# servos.net
KiCad netlist of a schematic drawn in Altium Designer
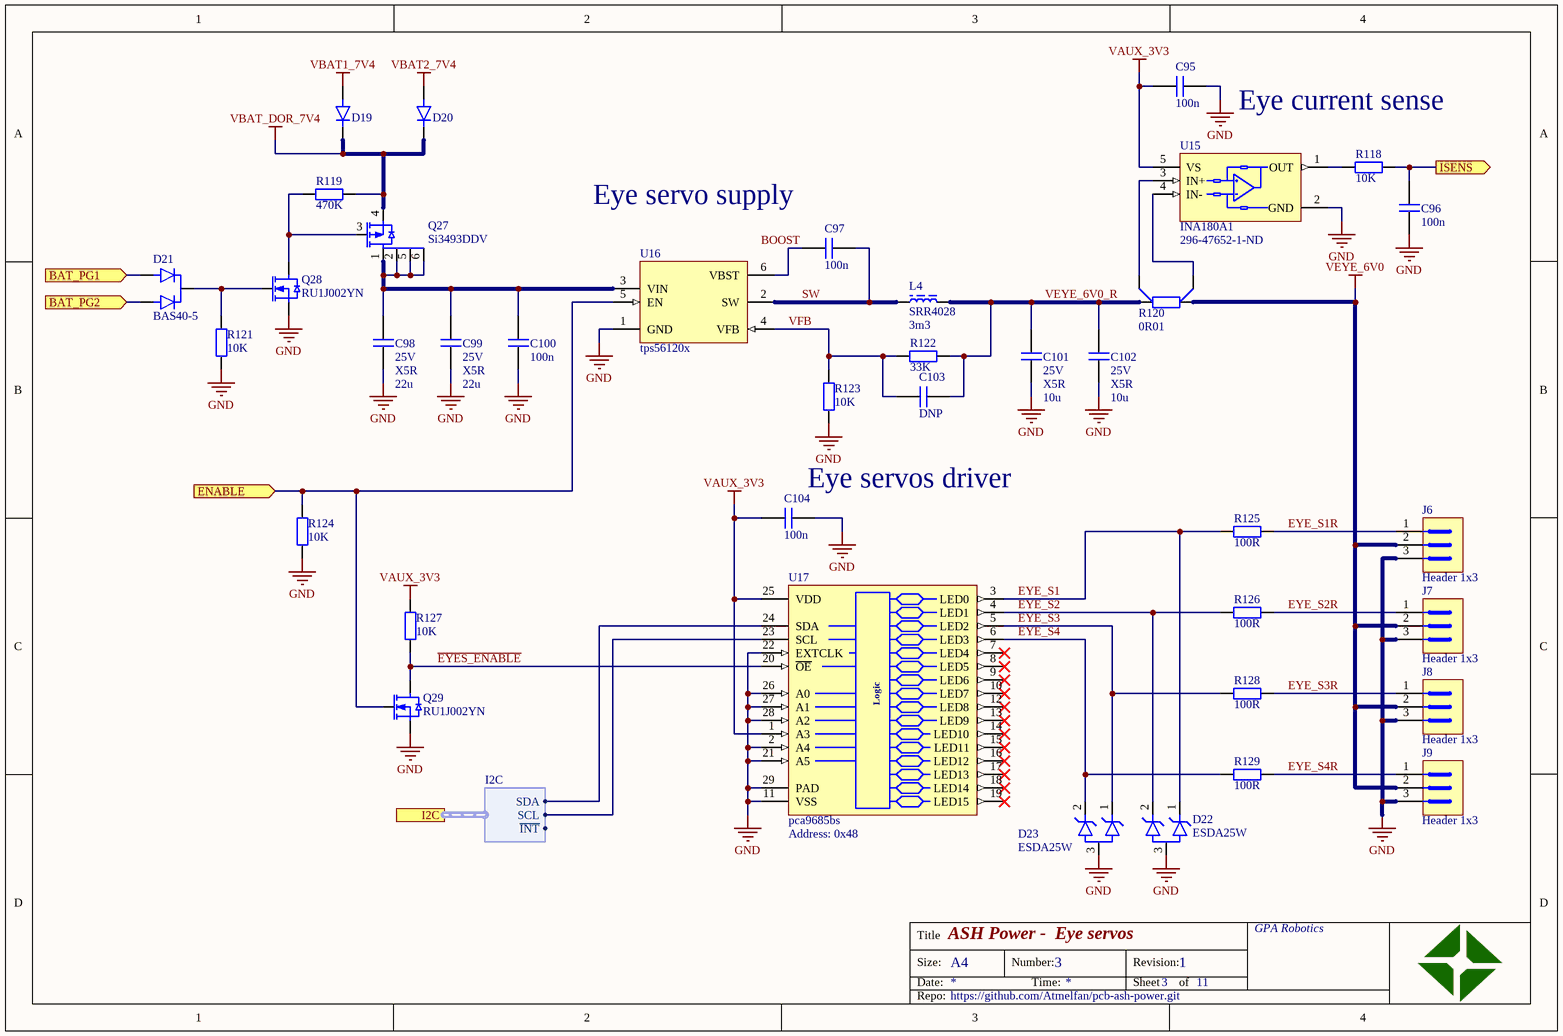
[diagram p0: servos.SchDoc]

(export (version "E")
  (design (tool "Eeschema 10.0.6"))
  (components
    (comp (ref "C95")
      (value "100n")
      (footprint "CAPC1005X06N")
      (description "Capacitor")
      (fields (field (name "Comment") "cap"))
      (libsource (lib "lib_passives") (part "cap"))
    )
    (comp (ref "C96")
      (value "100n")
      (footprint "CAPC1005X06N")
      (description "Capacitor")
      (fields (field (name "Comment") "cap"))
      (libsource (lib "lib_passives") (part "cap"))
    )
    (comp (ref "C97")
      (value "100n")
      (footprint "CAPC1005X06N")
      (description "Capacitor")
      (fields (field (name "Comment") "cap"))
      (libsource (lib "lib_passives") (part "cap"))
    )
    (comp (ref "C98")
      (value "22u")
      (footprint "CAPC3216X14N")
      (description "Capacitor")
      (fields (field (name "VOLTAGE") "25V") (field (name "TYPE") "X5R") (field (name "Comment") "cap"))
      (libsource (lib "lib_passives") (part "cap"))
    )
    (comp (ref "C99")
      (value "22u")
      (footprint "CAPC3216X14N")
      (description "Capacitor")
      (fields (field (name "VOLTAGE") "25V") (field (name "TYPE") "X5R") (field (name "Comment") "cap"))
      (libsource (lib "lib_passives") (part "cap"))
    )
    (comp (ref "C100")
      (value "100n")
      (footprint "CAPC1005X06N")
      (description "Capacitor")
      (fields (field (name "Comment") "cap"))
      (libsource (lib "lib_passives") (part "cap"))
    )
    (comp (ref "C101")
      (value "10u")
      (footprint "CAPC3216X14N")
      (description "Capacitor")
      (fields (field (name "VOLTAGE") "25V") (field (name "TYPE") "X5R") (field (name "Comment") "cap"))
      (libsource (lib "lib_passives") (part "cap"))
    )
    (comp (ref "C102")
      (value "10u")
      (footprint "CAPC3216X14N")
      (description "Capacitor")
      (fields (field (name "VOLTAGE") "25V") (field (name "TYPE") "X5R") (field (name "Comment") "cap"))
      (libsource (lib "lib_passives") (part "cap"))
    )
    (comp (ref "C103")
      (value "DNP")
      (footprint "CAPC1005X06N")
      (description "Capacitor")
      (fields (field (name "Comment") "cap"))
      (libsource (lib "lib_passives") (part "cap"))
    )
    (comp (ref "C104")
      (value "100n")
      (footprint "CAPC1005X06N")
      (description "Capacitor")
      (fields (field (name "Comment") "cap"))
      (libsource (lib "lib_passives") (part "cap"))
    )
    (comp (ref "D19")
      (value "DFLS2100")
      (footprint "SODFL370X100-2N_DFLS2100")
      (description "2.0A HIGH VOLTAGE SCHOTTKY BARRIER RECTIFIER")
      (libsource (lib "lib_diodesinc") (part "dfls2100"))
    )
    (comp (ref "D20")
      (value "DFLS2100")
      (footprint "SODFL370X100-2N_DFLS2100")
      (description "2.0A HIGH VOLTAGE SCHOTTKY BARRIER RECTIFIER")
      (libsource (lib "lib_diodesinc") (part "dfls2100"))
    )
    (comp (ref "D21")
      (value "BAS40-5")
      (footprint "SOT23_CC")
      (description "Diode Common Cathode")
      (libsource (lib "lib_actives") (part "diode_dual_cc"))
    )
    (comp (ref "D22")
      (value "ESDA25W")
      (footprint "SOT65P210X110-3N_SOT323-3L")
      (description "TRANSIL array for data protection")
      (libsource (lib "lib_st") (part "esda25w"))
    )
    (comp (ref "D23")
      (value "ESDA25W")
      (footprint "SOT65P210X110-3N_SOT323-3L")
      (description "TRANSIL array for data protection")
      (libsource (lib "lib_st") (part "esda25w"))
    )
    (comp (ref "J6")
      (value "Header 1x3")
      (footprint "HEADER_1x3_100MIL")
      (description "2.54mm pitch single row header")
      (libsource (lib "lib_connectors") (part "header_1x3_100mil"))
    )
    (comp (ref "J7")
      (value "Header 1x3")
      (footprint "HEADER_1x3_100MIL")
      (description "2.54mm pitch single row header")
      (libsource (lib "lib_connectors") (part "header_1x3_100mil"))
    )
    (comp (ref "J8")
      (value "Header 1x3")
      (footprint "HEADER_1x3_100MIL")
      (description "2.54mm pitch single row header")
      (libsource (lib "lib_connectors") (part "header_1x3_100mil"))
    )
    (comp (ref "J9")
      (value "Header 1x3")
      (footprint "HEADER_1x3_100MIL")
      (description "2.54mm pitch single row header")
      (libsource (lib "lib_connectors") (part "header_1x3_100mil"))
    )
    (comp (ref "L4")
      (value "SRR4028")
      (footprint "SRR4028")
      (fields (field (name "ALTIUM_VALUE") "3m3"))
      (libsource (lib "lib_bourns") (part "srr4028"))
    )
    (comp (ref "Q27")
      (value "Si3493DDV")
      (footprint "SOT95P284X110-6N_TSOP6")
      (description "P-Channel 20 V (D-S) MOSFET")
      (libsource (lib "lib_vishay") (part "si3493ddv"))
    )
    (comp (ref "Q28")
      (value "RU1J002YN")
      (footprint "SOTFL65P210X105-3N")
      (description "N-channel 50V 200mA Small signal MOSFET")
      (libsource (lib "lib_rohm") (part "ru1j002yn"))
    )
    (comp (ref "Q29")
      (value "RU1J002YN")
      (footprint "SOTFL65P210X105-3N")
      (description "N-channel 50V 200mA Small signal MOSFET")
      (libsource (lib "lib_rohm") (part "ru1j002yn"))
    )
    (comp (ref "R118")
      (value "10K")
      (footprint "RESC1005X04N")
      (description "Resistor")
      (fields (field (name "Comment") "res"))
      (libsource (lib "lib_passives") (part "res"))
    )
    (comp (ref "R119")
      (value "470K")
      (footprint "RESC1005X04N")
      (description "Resistor")
      (fields (field (name "Comment") "res"))
      (libsource (lib "lib_passives") (part "res"))
    )
    (comp (ref "R120")
      (value "0R01")
      (footprint "4T_RESC1632X05N")
      (description "Resistor")
      (fields (field (name "Comment") "res_4t"))
      (libsource (lib "lib_passives") (part "res_4t"))
    )
    (comp (ref "R121")
      (value "10K")
      (footprint "RESC1005X04N")
      (description "Resistor")
      (fields (field (name "Comment") "res"))
      (libsource (lib "") (part "res_1"))
    )
    (comp (ref "R122")
      (value "33K")
      (footprint "RESC1005X04N")
      (description "Resistor")
      (fields (field (name "Comment") "res"))
      (libsource (lib "lib_passives") (part "res"))
    )
    (comp (ref "R123")
      (value "10K")
      (footprint "RESC1005X04N")
      (description "Resistor")
      (fields (field (name "Comment") "res"))
      (libsource (lib "") (part "res_1"))
    )
    (comp (ref "R124")
      (value "10K")
      (footprint "RESC1005X04N")
      (description "Resistor")
      (fields (field (name "Comment") "res"))
      (libsource (lib "") (part "res_1"))
    )
    (comp (ref "R125")
      (value "100R")
      (footprint "RESC1005X04N")
      (description "Resistor")
      (fields (field (name "Comment") "res"))
      (libsource (lib "lib_passives") (part "res"))
    )
    (comp (ref "R126")
      (value "100R")
      (footprint "RESC1005X04N")
      (description "Resistor")
      (fields (field (name "Comment") "res"))
      (libsource (lib "lib_passives") (part "res"))
    )
    (comp (ref "R127")
      (value "10K")
      (footprint "RESC1005X04N")
      (description "Resistor")
      (fields (field (name "Comment") "res"))
      (libsource (lib "") (part "res_1"))
    )
    (comp (ref "R128")
      (value "100R")
      (footprint "RESC1005X04N")
      (description "Resistor")
      (fields (field (name "Comment") "res"))
      (libsource (lib "lib_passives") (part "res"))
    )
    (comp (ref "R129")
      (value "100R")
      (footprint "RESC1005X04N")
      (description "Resistor")
      (fields (field (name "Comment") "res"))
      (libsource (lib "lib_passives") (part "res"))
    )
    (comp (ref "U15")
      (value "INA180A1")
      (footprint "SOT95P280X145-5N")
      (description "Low- and High-Side Voltage Output, Current-Sense Amplifiers")
      (fields (field (name "SUPPLIER PART NUMBER 1") "296-47652-1-ND"))
      (libsource (lib "lib_ti") (part "ina180a1"))
    )
    (comp (ref "U16")
      (value "tps56120x")
      (footprint "SOT95P280X110-6N")
      (description "4.5-V to 17-V Input, 1-A Synchronous  Step-Down  Voltage  Regulator  in 6-Pin  SOT-23")
      (libsource (lib "lib_ti") (part "tps56120x"))
    )
    (comp (ref "U17")
      (value "pca9685bs")
      (footprint "QFN65P600X600X100_HS-29N_PCA9685BS")
      (description "16-channel, 12-bit PWM Fm+ I2C-bus LED controller")
      (fields (field (name "ADDRESS") "0x48"))
      (libsource (lib "lib_nxp") (part "pca9685bs"))
    )
  )
  (nets
    (net (code "2") (name "/BAT_PG1") (class "Default")
      (node (ref "D21") (pin "A1") (pinfunction "A1_A1") (pintype "passive"))
    )
    (net (code "3") (name "/BAT_PG2") (class "Default")
      (node (ref "D21") (pin "A2") (pinfunction "A2_A2") (pintype "passive"))
    )
    (net (code "4") (name "/BOOST") (class "Default")
      (node (ref "C97") (pin "1") (pinfunction "1_1") (pintype "passive"))
      (node (ref "U16") (pin "6") (pinfunction "VBST_6") (pintype "passive"))
    )
    (net (code "5") (name "/ENABLE") (class "Default")
      (node (ref "Q29") (pin "1") (pinfunction "G_1") (pintype "passive"))
      (node (ref "R124") (pin "2") (pinfunction "2_2") (pintype "passive"))
      (node (ref "U16") (pin "5") (pinfunction "EN_5") (pintype "input"))
    )
    (net (code "6") (name "/EYES_ENABLE") (class "Default")
      (node (ref "Q29") (pin "3") (pinfunction "D_3") (pintype "passive"))
      (node (ref "R127") (pin "1") (pinfunction "1_1") (pintype "passive"))
      (node (ref "U17") (pin "20") (pinfunction "OE_20") (pintype "input"))
    )
    (net (code "7") (name "/EYE_S1") (class "Default")
      (node (ref "D22") (pin "1") (pinfunction "1_1") (pintype "passive"))
      (node (ref "R125") (pin "1") (pinfunction "1_1") (pintype "passive"))
      (node (ref "U17") (pin "3") (pinfunction "LED0_3") (pintype "output"))
    )
    (net (code "8") (name "/EYE_S1R") (class "Default")
      (node (ref "J6") (pin "1") (pinfunction "1_1") (pintype "passive"))
      (node (ref "R125") (pin "2") (pinfunction "2_2") (pintype "passive"))
    )
    (net (code "9") (name "/EYE_S2") (class "Default")
      (node (ref "D22") (pin "2") (pinfunction "2_2") (pintype "passive"))
      (node (ref "R126") (pin "1") (pinfunction "1_1") (pintype "passive"))
      (node (ref "U17") (pin "4") (pinfunction "LED1_4") (pintype "output"))
    )
    (net (code "10") (name "/EYE_S2R") (class "Default")
      (node (ref "J7") (pin "1") (pinfunction "1_1") (pintype "passive"))
      (node (ref "R126") (pin "2") (pinfunction "2_2") (pintype "passive"))
    )
    (net (code "11") (name "/EYE_S3") (class "Default")
      (node (ref "D23") (pin "1") (pinfunction "1_1") (pintype "passive"))
      (node (ref "R128") (pin "1") (pinfunction "1_1") (pintype "passive"))
      (node (ref "U17") (pin "5") (pinfunction "LED2_5") (pintype "output"))
    )
    (net (code "12") (name "/EYE_S3R") (class "Default")
      (node (ref "J8") (pin "1") (pinfunction "1_1") (pintype "passive"))
      (node (ref "R128") (pin "2") (pinfunction "2_2") (pintype "passive"))
    )
    (net (code "13") (name "/EYE_S4") (class "Default")
      (node (ref "D23") (pin "2") (pinfunction "2_2") (pintype "passive"))
      (node (ref "R129") (pin "1") (pinfunction "1_1") (pintype "passive"))
      (node (ref "U17") (pin "6") (pinfunction "LED3_6") (pintype "output"))
    )
    (net (code "14") (name "/EYE_S4R") (class "Default")
      (node (ref "J9") (pin "1") (pinfunction "1_1") (pintype "passive"))
      (node (ref "R129") (pin "2") (pinfunction "2_2") (pintype "passive"))
    )
    (net (code "15") (name "/ISENS") (class "Default")
      (node (ref "C96") (pin "2") (pinfunction "2_2") (pintype "passive"))
      (node (ref "R118") (pin "2") (pinfunction "2_2") (pintype "passive"))
    )
    (net (code "16") (name "/SCL") (class "Default")
      (node (ref "U17") (pin "23") (pinfunction "SCL_23") (pintype "open_collector"))
    )
    (net (code "17") (name "/SDA") (class "Default")
      (node (ref "U17") (pin "24") (pinfunction "SDA_24") (pintype "open_collector"))
    )
    (net (code "18") (name "/SW") (class "Default")
      (node (ref "C97") (pin "2") (pinfunction "2_2") (pintype "passive"))
      (node (ref "L4") (pin "1") (pinfunction "1_1") (pintype "passive"))
      (node (ref "U16") (pin "2") (pinfunction "SW_2") (pintype "power_in"))
    )
    (net (code "19") (name "/VEYE_6V0_R") (class "Default")
      (node (ref "C101") (pin "2") (pinfunction "2_2") (pintype "passive"))
      (node (ref "C102") (pin "2") (pinfunction "2_2") (pintype "passive"))
      (node (ref "C103") (pin "2") (pinfunction "2_2") (pintype "passive"))
      (node (ref "L4") (pin "2") (pinfunction "2_2") (pintype "passive"))
      (node (ref "R120") (pin "1") (pinfunction "1_1") (pintype "passive"))
      (node (ref "R122") (pin "2") (pinfunction "2_2") (pintype "passive"))
    )
    (net (code "20") (name "/VFB") (class "Default")
      (node (ref "C103") (pin "1") (pinfunction "1_1") (pintype "passive"))
      (node (ref "R122") (pin "1") (pinfunction "1_1") (pintype "passive"))
      (node (ref "R123") (pin "2") (pinfunction "2_2") (pintype "passive"))
      (node (ref "U16") (pin "4") (pinfunction "VFB_4") (pintype "input"))
    )
    (net (code "22") (name "GND") (class "Default")
      (node (ref "C100") (pin "1") (pinfunction "1_1") (pintype "passive"))
      (node (ref "C101") (pin "1") (pinfunction "1_1") (pintype "passive"))
      (node (ref "C102") (pin "1") (pinfunction "1_1") (pintype "passive"))
      (node (ref "C104") (pin "2") (pinfunction "2_2") (pintype "passive"))
      (node (ref "C95") (pin "1") (pinfunction "1_1") (pintype "passive"))
      (node (ref "C96") (pin "1") (pinfunction "1_1") (pintype "passive"))
      (node (ref "C98") (pin "1") (pinfunction "1_1") (pintype "passive"))
      (node (ref "C99") (pin "1") (pinfunction "1_1") (pintype "passive"))
      (node (ref "D22") (pin "3") (pinfunction "3_3") (pintype "passive"))
      (node (ref "D23") (pin "3") (pinfunction "3_3") (pintype "passive"))
      (node (ref "J6") (pin "3") (pinfunction "3_3") (pintype "passive"))
      (node (ref "J7") (pin "3") (pinfunction "3_3") (pintype "passive"))
      (node (ref "J8") (pin "3") (pinfunction "3_3") (pintype "passive"))
      (node (ref "J9") (pin "3") (pinfunction "3_3") (pintype "passive"))
      (node (ref "Q28") (pin "2") (pinfunction "S_2") (pintype "passive"))
      (node (ref "Q29") (pin "2") (pinfunction "S_2") (pintype "passive"))
      (node (ref "R121") (pin "1") (pinfunction "1_1") (pintype "passive"))
      (node (ref "R123") (pin "1") (pinfunction "1_1") (pintype "passive"))
      (node (ref "R124") (pin "1") (pinfunction "1_1") (pintype "passive"))
      (node (ref "U15") (pin "2") (pinfunction "GND_2") (pintype "power_in"))
      (node (ref "U16") (pin "1") (pinfunction "GND_1") (pintype "power_in"))
      (node (ref "U17") (pin "11") (pinfunction "VSS_11") (pintype "power_in"))
      (node (ref "U17") (pin "2") (pinfunction "A4_2") (pintype "input"))
      (node (ref "U17") (pin "21") (pinfunction "A5_21") (pintype "input"))
      (node (ref "U17") (pin "22") (pinfunction "EXTCLK_22") (pintype "input"))
      (node (ref "U17") (pin "26") (pinfunction "A0_26") (pintype "input"))
      (node (ref "U17") (pin "27") (pinfunction "A1_27") (pintype "input"))
      (node (ref "U17") (pin "28") (pinfunction "A2_28") (pintype "input"))
      (node (ref "U17") (pin "29") (pinfunction "PAD_29") (pintype "power_in"))
    )
    (net (code "23") (name "Net-(Q27-G)") (class "Default")
      (node (ref "Q27") (pin "3") (pinfunction "G_3") (pintype "passive"))
      (node (ref "Q28") (pin "3") (pinfunction "D_3") (pintype "passive"))
      (node (ref "R119") (pin "1") (pinfunction "1_1") (pintype "passive"))
    )
    (net (code "24") (name "Net-(Q28-G)") (class "Default")
      (node (ref "D21") (pin "C") (pinfunction "C_C") (pintype "passive"))
      (node (ref "Q28") (pin "1") (pinfunction "G_1") (pintype "passive"))
      (node (ref "R121") (pin "2") (pinfunction "2_2") (pintype "passive"))
    )
    (net (code "25") (name "Net-(U15-IN+)") (class "Default")
      (node (ref "R120") (pin "3") (pinfunction "3_3") (pintype "passive"))
      (node (ref "U15") (pin "3") (pinfunction "IN+_3") (pintype "input"))
    )
    (net (code "26") (name "Net-(U15-IN-)") (class "Default")
      (node (ref "R120") (pin "4") (pinfunction "4_4") (pintype "passive"))
      (node (ref "U15") (pin "4") (pinfunction "IN-_4") (pintype "input"))
    )
    (net (code "27") (name "Net-(U15-OUT)") (class "Default")
      (node (ref "R118") (pin "1") (pinfunction "1_1") (pintype "passive"))
      (node (ref "U15") (pin "1") (pinfunction "OUT_1") (pintype "output"))
    )
    (net (code "28") (name "Net-(U16-VIN)") (class "Default")
      (node (ref "C100") (pin "2") (pinfunction "2_2") (pintype "passive"))
      (node (ref "C98") (pin "2") (pinfunction "2_2") (pintype "passive"))
      (node (ref "C99") (pin "2") (pinfunction "2_2") (pintype "passive"))
      (node (ref "Q27") (pin "1") (pinfunction "D_1") (pintype "passive"))
      (node (ref "Q27") (pin "2") (pinfunction "D_2") (pintype "passive"))
      (node (ref "Q27") (pin "5") (pinfunction "D_5") (pintype "passive"))
      (node (ref "Q27") (pin "6") (pinfunction "D_6") (pintype "passive"))
      (node (ref "U16") (pin "3") (pinfunction "VIN_3") (pintype "power_in"))
    )
    (net (code "29") (name "VAUX_3V3") (class "Default")
      (node (ref "C104") (pin "1") (pinfunction "1_1") (pintype "passive"))
      (node (ref "C95") (pin "2") (pinfunction "2_2") (pintype "passive"))
      (node (ref "R127") (pin "2") (pinfunction "2_2") (pintype "passive"))
      (node (ref "U15") (pin "5") (pinfunction "VS_5") (pintype "power_in"))
      (node (ref "U17") (pin "1") (pinfunction "A3_1") (pintype "input"))
      (node (ref "U17") (pin "25") (pinfunction "VDD_25") (pintype "power_in"))
    )
    (net (code "30") (name "VBAT1_7V4") (class "Default")
      (node (ref "D19") (pin "A") (pinfunction "A_A") (pintype "passive"))
    )
    (net (code "31") (name "VBAT2_7V4") (class "Default")
      (node (ref "D20") (pin "A") (pinfunction "A_A") (pintype "passive"))
    )
    (net (code "32") (name "VBAT_DOR_7V4") (class "Default")
      (node (ref "D19") (pin "C") (pinfunction "C_C") (pintype "passive"))
      (node (ref "D20") (pin "C") (pinfunction "C_C") (pintype "passive"))
      (node (ref "Q27") (pin "4") (pinfunction "S_4") (pintype "passive"))
      (node (ref "R119") (pin "2") (pinfunction "2_2") (pintype "passive"))
    )
    (net (code "33") (name "VEYE_6V0") (class "Default")
      (node (ref "J6") (pin "2") (pinfunction "2_2") (pintype "passive"))
      (node (ref "J7") (pin "2") (pinfunction "2_2") (pintype "passive"))
      (node (ref "J8") (pin "2") (pinfunction "2_2") (pintype "passive"))
      (node (ref "J9") (pin "2") (pinfunction "2_2") (pintype "passive"))
      (node (ref "R120") (pin "2") (pinfunction "2_2") (pintype "passive"))
    )
    (net (code "34") (name "unconnected-(U17-LED4-Pad7)") (class "Default")
      (node (ref "U17") (pin "7") (pinfunction "LED4_7") (pintype "output+no_connect"))
    )
    (net (code "35") (name "unconnected-(U17-LED5-Pad8)") (class "Default")
      (node (ref "U17") (pin "8") (pinfunction "LED5_8") (pintype "output+no_connect"))
    )
    (net (code "36") (name "unconnected-(U17-LED6-Pad9)") (class "Default")
      (node (ref "U17") (pin "9") (pinfunction "LED6_9") (pintype "output+no_connect"))
    )
    (net (code "37") (name "unconnected-(U17-LED7-Pad10)") (class "Default")
      (node (ref "U17") (pin "10") (pinfunction "LED7_10") (pintype "output+no_connect"))
    )
    (net (code "38") (name "unconnected-(U17-LED8-Pad12)") (class "Default")
      (node (ref "U17") (pin "12") (pinfunction "LED8_12") (pintype "output+no_connect"))
    )
    (net (code "39") (name "unconnected-(U17-LED9-Pad13)") (class "Default")
      (node (ref "U17") (pin "13") (pinfunction "LED9_13") (pintype "output+no_connect"))
    )
    (net (code "40") (name "unconnected-(U17-LED10-Pad14)") (class "Default")
      (node (ref "U17") (pin "14") (pinfunction "LED10_14") (pintype "output+no_connect"))
    )
    (net (code "41") (name "unconnected-(U17-LED11-Pad15)") (class "Default")
      (node (ref "U17") (pin "15") (pinfunction "LED11_15") (pintype "output+no_connect"))
    )
    (net (code "42") (name "unconnected-(U17-LED12-Pad16)") (class "Default")
      (node (ref "U17") (pin "16") (pinfunction "LED12_16") (pintype "output+no_connect"))
    )
    (net (code "43") (name "unconnected-(U17-LED13-Pad17)") (class "Default")
      (node (ref "U17") (pin "17") (pinfunction "LED13_17") (pintype "output+no_connect"))
    )
    (net (code "44") (name "unconnected-(U17-LED14-Pad18)") (class "Default")
      (node (ref "U17") (pin "18") (pinfunction "LED14_18") (pintype "output+no_connect"))
    )
    (net (code "45") (name "unconnected-(U17-LED15-Pad19)") (class "Default")
      (node (ref "U17") (pin "19") (pinfunction "LED15_19") (pintype "output+no_connect"))
    )
  )
)
